# esquematico.net
KiCad netlist of a schematic drawn in EAGLE
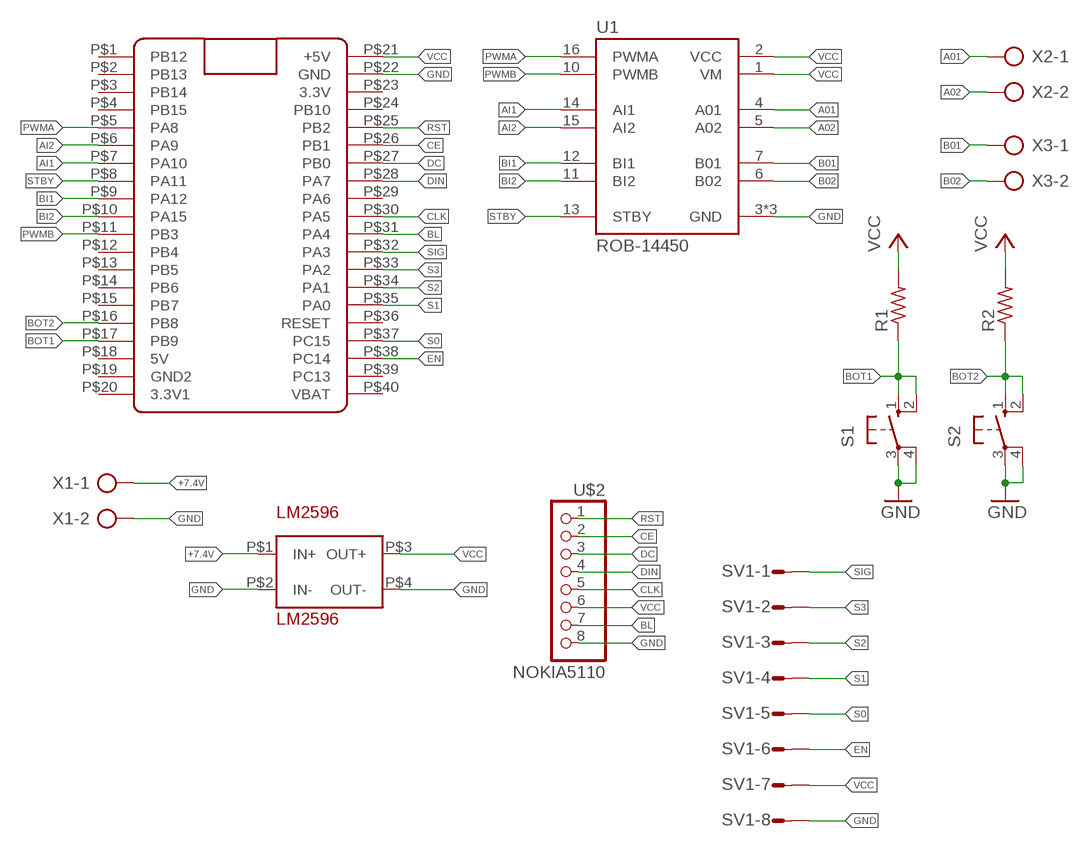
[diagram p0: schematic, sheet 1]

(export (version "E")
  (design (tool "Eeschema 10.0.6"))
  (components
    (comp (ref "R1")
      (value "R-US_0204/7")
      (footprint "eagle-import:0204_7")
      (libsource (lib "eagle-import") (part "R-US_0204/7"))
    )
    (comp (ref "R2")
      (value "R-US_0204/7")
      (footprint "eagle-import:0204_7")
      (libsource (lib "eagle-import") (part "R-US_0204/7"))
    )
    (comp (ref "S1")
      (value "10-XX")
      (footprint "eagle-import:B3F-10XX")
      (fields (field (name "MPN") "B3F-1000"))
      (libsource (lib "eagle-import") (part "10-XX"))
    )
    (comp (ref "S2")
      (value "10-XX")
      (footprint "eagle-import:B3F-10XX")
      (fields (field (name "MPN") "B3F-1000"))
      (libsource (lib "eagle-import") (part "10-XX"))
    )
    (comp (ref "SV1")
      (value "S08P")
      (footprint "eagle-import:S08P")
      (libsource (lib "eagle-import") (part "S08P"))
    )
    (comp (ref "U$1")
      (value "BLUE_PILL")
      (footprint "eagle-import:BLUE_PILL")
      (libsource (lib "eagle-import") (part "BLUE_PILL"))
    )
    (comp (ref "U$2")
      (value "NOKIA5110")
      (footprint "eagle-import:1X08")
      (libsource (lib "eagle-import") (part "NOKIA5110"))
    )
    (comp (ref "U$3")
      (value "LM2596")
      (footprint "eagle-import:LM2596")
      (libsource (lib "eagle-import") (part "LM2596"))
    )
    (comp (ref "U1")
      (value "ROB-14450")
      (footprint "eagle-import:MODULE_ROB-14450")
      (fields (field (name "MF") "SparkFun Electronics"))
      (libsource (lib "eagle-import") (part "ROB-14450"))
    )
    (comp (ref "X1")
      (value "AK300/2")
      (footprint "eagle-import:AK300_2")
      (libsource (lib "eagle-import") (part "AK300/2"))
    )
    (comp (ref "X2")
      (value "AK300/2")
      (footprint "eagle-import:AK300_2")
      (libsource (lib "eagle-import") (part "AK300/2"))
    )
    (comp (ref "X3")
      (value "AK300/2")
      (footprint "eagle-import:AK300_2")
      (libsource (lib "eagle-import") (part "AK300/2"))
    )
  )
  (nets
    (net (code "1") (name "+7.4V") (class "Default")
      (node (ref "U$3") (pin "P$1") (pinfunction "IN+_P$1") (pintype "bidirectional"))
      (node (ref "X1") (pin "1") (pinfunction "KL_1") (pintype "passive"))
    )
    (net (code "2") (name "A01") (class "Default")
      (node (ref "U1") (pin "4") (pinfunction "A01_4") (pintype "output"))
      (node (ref "X2") (pin "1") (pinfunction "KL_1") (pintype "passive"))
    )
    (net (code "3") (name "A02") (class "Default")
      (node (ref "U1") (pin "5") (pinfunction "A02_5") (pintype "output"))
      (node (ref "X2") (pin "2") (pinfunction "KL_2") (pintype "passive"))
    )
    (net (code "4") (name "AI1") (class "Default")
      (node (ref "U$1") (pin "P$7") (pinfunction "PA10_P$7") (pintype "bidirectional"))
      (node (ref "U1") (pin "14") (pinfunction "AI1_14") (pintype "input"))
    )
    (net (code "5") (name "AI2") (class "Default")
      (node (ref "U$1") (pin "P$6") (pinfunction "PA9_P$6") (pintype "bidirectional"))
      (node (ref "U1") (pin "15") (pinfunction "AI2_15") (pintype "input"))
    )
    (net (code "6") (name "B01") (class "Default")
      (node (ref "U1") (pin "7") (pinfunction "B01_7") (pintype "output"))
      (node (ref "X3") (pin "1") (pinfunction "KL_1") (pintype "passive"))
    )
    (net (code "7") (name "B02") (class "Default")
      (node (ref "U1") (pin "6") (pinfunction "B02_6") (pintype "output"))
      (node (ref "X3") (pin "2") (pinfunction "KL_2") (pintype "passive"))
    )
    (net (code "8") (name "BI1") (class "Default")
      (node (ref "U$1") (pin "P$9") (pinfunction "PA12_P$9") (pintype "bidirectional"))
      (node (ref "U1") (pin "12") (pinfunction "BI1_12") (pintype "input"))
    )
    (net (code "9") (name "BI2") (class "Default")
      (node (ref "U$1") (pin "P$10") (pinfunction "PA15_P$10") (pintype "bidirectional"))
      (node (ref "U1") (pin "11") (pinfunction "BI2_11") (pintype "input"))
    )
    (net (code "10") (name "BL") (class "Default")
      (node (ref "U$1") (pin "P$31") (pinfunction "PA4_P$31") (pintype "bidirectional"))
      (node (ref "U$2") (pin "7") (pinfunction "7_7") (pintype "passive"))
    )
    (net (code "11") (name "BOT1") (class "Default")
      (node (ref "R1") (pin "1") (pinfunction "1_1") (pintype "passive"))
      (node (ref "S1") (pin "1") (pinfunction "S_1") (pintype "passive"))
      (node (ref "S1") (pin "2") (pinfunction "S1_2") (pintype "passive"))
      (node (ref "U$1") (pin "P$17") (pinfunction "PB9_P$17") (pintype "bidirectional"))
    )
    (net (code "12") (name "BOT2") (class "Default")
      (node (ref "R2") (pin "1") (pinfunction "1_1") (pintype "passive"))
      (node (ref "S2") (pin "1") (pinfunction "S_1") (pintype "passive"))
      (node (ref "S2") (pin "2") (pinfunction "S1_2") (pintype "passive"))
      (node (ref "U$1") (pin "P$16") (pinfunction "PB8_P$16") (pintype "bidirectional"))
    )
    (net (code "13") (name "CE") (class "Default")
      (node (ref "U$1") (pin "P$26") (pinfunction "PB1_P$26") (pintype "bidirectional"))
      (node (ref "U$2") (pin "2") (pinfunction "2_2") (pintype "passive"))
    )
    (net (code "14") (name "CLK") (class "Default")
      (node (ref "U$1") (pin "P$30") (pinfunction "PA5_P$30") (pintype "bidirectional"))
      (node (ref "U$2") (pin "5") (pinfunction "5_5") (pintype "passive"))
    )
    (net (code "15") (name "DC") (class "Default")
      (node (ref "U$1") (pin "P$27") (pinfunction "PB0_P$27") (pintype "bidirectional"))
      (node (ref "U$2") (pin "3") (pinfunction "3_3") (pintype "passive"))
    )
    (net (code "16") (name "DIN") (class "Default")
      (node (ref "U$1") (pin "P$28") (pinfunction "PA7_P$28") (pintype "bidirectional"))
      (node (ref "U$2") (pin "4") (pinfunction "4_4") (pintype "passive"))
    )
    (net (code "17") (name "EN") (class "Default")
      (node (ref "SV1") (pin "6") (pinfunction "S_6") (pintype "passive"))
      (node (ref "U$1") (pin "P$38") (pinfunction "PC14_P$38") (pintype "bidirectional"))
    )
    (net (code "18") (name "GND") (class "Default")
      (node (ref "S1") (pin "3") (pinfunction "P_3") (pintype "passive"))
      (node (ref "S1") (pin "4") (pinfunction "P1_4") (pintype "passive"))
      (node (ref "S2") (pin "3") (pinfunction "P_3") (pintype "passive"))
      (node (ref "S2") (pin "4") (pinfunction "P1_4") (pintype "passive"))
      (node (ref "SV1") (pin "8") (pinfunction "S_8") (pintype "passive"))
      (node (ref "U$1") (pin "P$22") (pinfunction "GND_P$22") (pintype "bidirectional"))
      (node (ref "U$2") (pin "8") (pinfunction "8_8") (pintype "passive"))
      (node (ref "U$3") (pin "P$2") (pinfunction "IN-_P$2") (pintype "bidirectional"))
      (node (ref "U$3") (pin "P$4") (pinfunction "OUT-_P$4") (pintype "bidirectional"))
      (node (ref "U1") (pin "3") (pinfunction "GND_3") (pintype "power_in"))
      (node (ref "U1") (pin "8") (pinfunction "GND_8") (pintype "power_in"))
      (node (ref "U1") (pin "9") (pinfunction "GND_9") (pintype "power_in"))
      (node (ref "X1") (pin "2") (pinfunction "KL_2") (pintype "passive"))
    )
    (net (code "19") (name "PWMA") (class "Default")
      (node (ref "U$1") (pin "P$5") (pinfunction "PA8_P$5") (pintype "bidirectional"))
      (node (ref "U1") (pin "16") (pinfunction "PWMA_16") (pintype "input"))
    )
    (net (code "20") (name "PWMB") (class "Default")
      (node (ref "U$1") (pin "P$11") (pinfunction "PB3_P$11") (pintype "bidirectional"))
      (node (ref "U1") (pin "10") (pinfunction "PWMB_10") (pintype "input"))
    )
    (net (code "21") (name "RST") (class "Default")
      (node (ref "U$1") (pin "P$25") (pinfunction "PB2_P$25") (pintype "bidirectional"))
      (node (ref "U$2") (pin "1") (pinfunction "1_1") (pintype "passive"))
    )
    (net (code "22") (name "S0") (class "Default")
      (node (ref "SV1") (pin "5") (pinfunction "S_5") (pintype "passive"))
      (node (ref "U$1") (pin "P$37") (pinfunction "PC15_P$37") (pintype "bidirectional"))
    )
    (net (code "23") (name "S1") (class "Default")
      (node (ref "SV1") (pin "4") (pinfunction "S_4") (pintype "passive"))
      (node (ref "U$1") (pin "P$35") (pinfunction "PA0_P$35") (pintype "bidirectional"))
    )
    (net (code "24") (name "S2") (class "Default")
      (node (ref "SV1") (pin "3") (pinfunction "S_3") (pintype "passive"))
      (node (ref "U$1") (pin "P$34") (pinfunction "PA1_P$34") (pintype "bidirectional"))
    )
    (net (code "25") (name "S3") (class "Default")
      (node (ref "SV1") (pin "2") (pinfunction "S_2") (pintype "passive"))
      (node (ref "U$1") (pin "P$33") (pinfunction "PA2_P$33") (pintype "bidirectional"))
    )
    (net (code "26") (name "SIG") (class "Default")
      (node (ref "SV1") (pin "1") (pinfunction "S_1") (pintype "passive"))
      (node (ref "U$1") (pin "P$32") (pinfunction "PA3_P$32") (pintype "bidirectional"))
    )
    (net (code "27") (name "STBY") (class "Default")
      (node (ref "U$1") (pin "P$8") (pinfunction "PA11_P$8") (pintype "bidirectional"))
      (node (ref "U1") (pin "13") (pinfunction "STBY_13") (pintype "input"))
    )
    (net (code "28") (name "VCC") (class "Default")
      (node (ref "R1") (pin "2") (pinfunction "2_2") (pintype "passive"))
      (node (ref "R2") (pin "2") (pinfunction "2_2") (pintype "passive"))
      (node (ref "SV1") (pin "7") (pinfunction "S_7") (pintype "passive"))
      (node (ref "U$1") (pin "P$21") (pinfunction "+5V_P$21") (pintype "power_in"))
      (node (ref "U$2") (pin "6") (pinfunction "6_6") (pintype "passive"))
      (node (ref "U$3") (pin "P$3") (pinfunction "OUT+_P$3") (pintype "bidirectional"))
      (node (ref "U1") (pin "1") (pinfunction "VM_1") (pintype "power_in"))
      (node (ref "U1") (pin "2") (pinfunction "VCC_2") (pintype "power_in"))
    )
    (net (code "29") (name "unconnected-(U$1-3.3V-PadP$23)") (class "Default")
      (node (ref "U$1") (pin "P$23") (pinfunction "3.3V_P$23") (pintype "bidirectional"))
    )
    (net (code "30") (name "unconnected-(U$1-3.3V1-PadP$20)") (class "Default")
      (node (ref "U$1") (pin "P$20") (pinfunction "3.3V1_P$20") (pintype "bidirectional"))
    )
    (net (code "31") (name "unconnected-(U$1-5V-PadP$18)") (class "Default")
      (node (ref "U$1") (pin "P$18") (pinfunction "5V_P$18") (pintype "bidirectional"))
    )
    (net (code "32") (name "unconnected-(U$1-GND2-PadP$19)") (class "Default")
      (node (ref "U$1") (pin "P$19") (pinfunction "GND2_P$19") (pintype "bidirectional"))
    )
    (net (code "33") (name "unconnected-(U$1-PA6-PadP$29)") (class "Default")
      (node (ref "U$1") (pin "P$29") (pinfunction "PA6_P$29") (pintype "bidirectional"))
    )
    (net (code "34") (name "unconnected-(U$1-PB4-PadP$12)") (class "Default")
      (node (ref "U$1") (pin "P$12") (pinfunction "PB4_P$12") (pintype "bidirectional"))
    )
    (net (code "35") (name "unconnected-(U$1-PB5-PadP$13)") (class "Default")
      (node (ref "U$1") (pin "P$13") (pinfunction "PB5_P$13") (pintype "bidirectional"))
    )
    (net (code "36") (name "unconnected-(U$1-PB6-PadP$14)") (class "Default")
      (node (ref "U$1") (pin "P$14") (pinfunction "PB6_P$14") (pintype "bidirectional"))
    )
    (net (code "37") (name "unconnected-(U$1-PB7-PadP$15)") (class "Default")
      (node (ref "U$1") (pin "P$15") (pinfunction "PB7_P$15") (pintype "bidirectional"))
    )
    (net (code "38") (name "unconnected-(U$1-PB10-PadP$24)") (class "Default")
      (node (ref "U$1") (pin "P$24") (pinfunction "PB10_P$24") (pintype "bidirectional"))
    )
    (net (code "39") (name "unconnected-(U$1-PB12-PadP$1)") (class "Default")
      (node (ref "U$1") (pin "P$1") (pinfunction "PB12_P$1") (pintype "bidirectional"))
    )
    (net (code "40") (name "unconnected-(U$1-PB13-PadP$2)") (class "Default")
      (node (ref "U$1") (pin "P$2") (pinfunction "PB13_P$2") (pintype "bidirectional"))
    )
    (net (code "41") (name "unconnected-(U$1-PB14-PadP$3)") (class "Default")
      (node (ref "U$1") (pin "P$3") (pinfunction "PB14_P$3") (pintype "bidirectional"))
    )
    (net (code "42") (name "unconnected-(U$1-PB15-PadP$4)") (class "Default")
      (node (ref "U$1") (pin "P$4") (pinfunction "PB15_P$4") (pintype "bidirectional"))
    )
    (net (code "43") (name "unconnected-(U$1-PC13-PadP$39)") (class "Default")
      (node (ref "U$1") (pin "P$39") (pinfunction "PC13_P$39") (pintype "bidirectional"))
    )
    (net (code "44") (name "unconnected-(U$1-RESET-PadP$36)") (class "Default")
      (node (ref "U$1") (pin "P$36") (pinfunction "RESET_P$36") (pintype "bidirectional"))
    )
    (net (code "45") (name "unconnected-(U$1-VBAT-PadP$40)") (class "Default")
      (node (ref "U$1") (pin "P$40") (pinfunction "VBAT_P$40") (pintype "bidirectional"))
    )
  )
)
